# DC_link_2L.net
KiCad netlist of a schematic drawn in Altium Designer
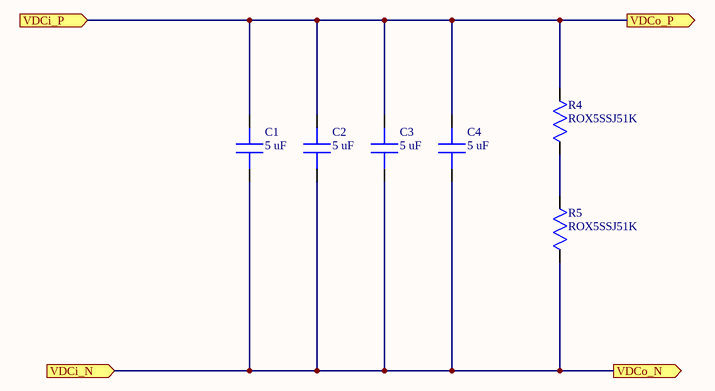
[diagram p0: DC_link_2L.SchDoc]

(export (version "E")
  (design (tool "Eeschema 10.0.6"))
  (components
    (comp (ref "C1")
      (value "MKP1848S55010JP4B")
      (footprint "MKP1848S55010JP4B")
      (description "Film Capacitors 5uF 5% 1000volts 4pins 37.5mm LS")
      (fields
        (field (name "TOLERANCE") "5 %")
        (field (name "MANUFACTURER") "Vishay")
        (field (name "CAPACITANCE") "5 uF")
      )
      (libsource (lib "Altium_Library_POWERLAB") (part "MKP1848S55010JP4B"))
    )
    (comp (ref "C2")
      (value "MKP1848S55010JP4B")
      (footprint "MKP1848S55010JP4B")
      (description "Film Capacitors 5uF 5% 1000volts 4pins 37.5mm LS")
      (fields
        (field (name "TOLERANCE") "5 %")
        (field (name "MANUFACTURER") "Vishay")
        (field (name "CAPACITANCE") "5 uF")
      )
      (libsource (lib "Altium_Library_POWERLAB") (part "MKP1848S55010JP4B"))
    )
    (comp (ref "C3")
      (value "MKP1848S55010JP4B")
      (footprint "MKP1848S55010JP4B")
      (description "Film Capacitors 5uF 5% 1000volts 4pins 37.5mm LS")
      (fields
        (field (name "TOLERANCE") "5 %")
        (field (name "MANUFACTURER") "Vishay")
        (field (name "CAPACITANCE") "5 uF")
      )
      (libsource (lib "Altium_Library_POWERLAB") (part "MKP1848S55010JP4B"))
    )
    (comp (ref "C4")
      (value "MKP1848S55010JP4B")
      (footprint "MKP1848S55010JP4B")
      (description "Film Capacitors 5uF 5% 1000volts 4pins 37.5mm LS")
      (fields
        (field (name "TOLERANCE") "5 %")
        (field (name "MANUFACTURER") "Vishay")
        (field (name "CAPACITANCE") "5 uF")
      )
      (libsource (lib "Altium_Library_POWERLAB") (part "MKP1848S55010JP4B"))
    )
    (comp (ref "R4")
      (value "ROX5SSJ51K")
      (footprint "RES_ROX5SS")
      (description "Metal Oxide Resistors 5W XSM M/OX 5% 51K")
      (fields (field (name "MANUFACTURER") "TE Connectivity") (field (name "POWER") "5 W"))
      (libsource (lib "Altium_Library_POWERLAB") (part "ROX5SSJ51K"))
    )
    (comp (ref "R5")
      (value "ROX5SSJ51K")
      (footprint "RES_ROX5SS")
      (description "Metal Oxide Resistors 5W XSM M/OX 5% 51K")
      (fields (field (name "MANUFACTURER") "TE Connectivity") (field (name "POWER") "5 W"))
      (libsource (lib "Altium_Library_POWERLAB") (part "ROX5SSJ51K"))
    )
  )
  (nets
    (net (code "1") (name "/VDCi_N") (class "Default")
      (node (ref "C1") (pin "2") (pinfunction "2_2") (pintype "passive"))
      (node (ref "C2") (pin "2") (pinfunction "2_2") (pintype "passive"))
      (node (ref "C3") (pin "2") (pinfunction "2_2") (pintype "passive"))
      (node (ref "C4") (pin "2") (pinfunction "2_2") (pintype "passive"))
      (node (ref "R5") (pin "1") (pinfunction "1_1") (pintype "passive"))
    )
    (net (code "2") (name "/VDCi_P") (class "Default")
      (node (ref "C1") (pin "1") (pinfunction "1_1") (pintype "passive"))
      (node (ref "C2") (pin "1") (pinfunction "1_1") (pintype "passive"))
      (node (ref "C3") (pin "1") (pinfunction "1_1") (pintype "passive"))
      (node (ref "C4") (pin "1") (pinfunction "1_1") (pintype "passive"))
      (node (ref "R4") (pin "2") (pinfunction "2_2") (pintype "passive"))
    )
    (net (code "3") (name "Net-(R4-Pad1)") (class "Default")
      (node (ref "R4") (pin "1") (pinfunction "1_1") (pintype "passive"))
      (node (ref "R5") (pin "2") (pinfunction "2_2") (pintype "passive"))
    )
  )
)
